# pcm5100_breakout_v10.net
KiCad netlist of a schematic drawn in EAGLE
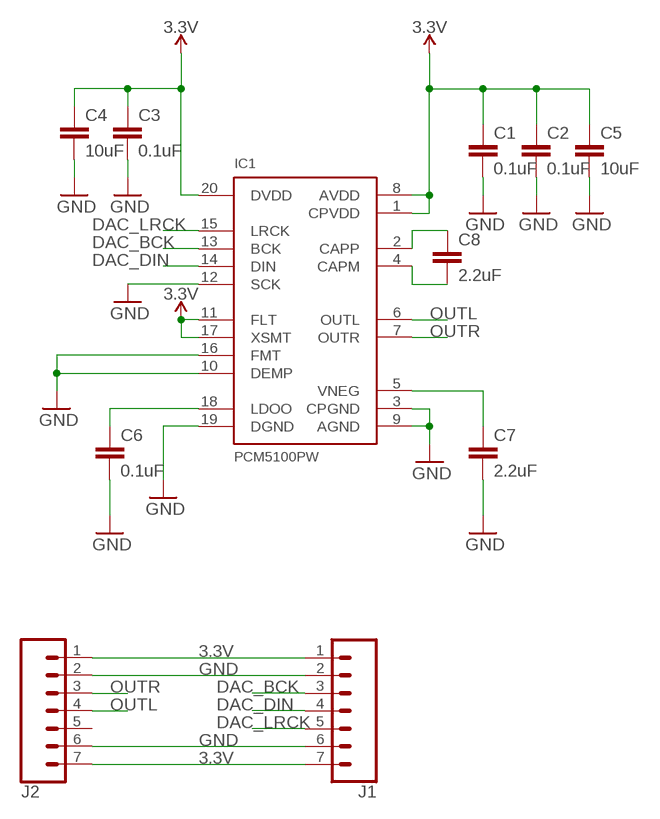
[diagram p0: schematic, sheet 1]

(export (version "E")
  (design (tool "Eeschema 10.0.6"))
  (components
    (comp (ref "C1")
      (value "0.1uF")
      (footprint "eagle-import:0603")
      (libsource (lib "eagle-import") (part "0.1UF-0603-25V-(+80/-20%)"))
    )
    (comp (ref "C2")
      (value "0.1uF")
      (footprint "eagle-import:0603")
      (libsource (lib "eagle-import") (part "0.1UF-0603-25V-(+80/-20%)"))
    )
    (comp (ref "C3")
      (value "0.1uF")
      (footprint "eagle-import:0603")
      (libsource (lib "eagle-import") (part "0.1UF-0603-25V-(+80/-20%)"))
    )
    (comp (ref "C4")
      (value "10uF")
      (footprint "eagle-import:0603")
      (libsource (lib "eagle-import") (part "10UF-0603-6.3V-20%"))
    )
    (comp (ref "C5")
      (value "10uF")
      (footprint "eagle-import:0603")
      (libsource (lib "eagle-import") (part "10UF-0603-6.3V-20%"))
    )
    (comp (ref "C6")
      (value "0.1uF")
      (footprint "eagle-import:0603")
      (libsource (lib "eagle-import") (part "0.1UF-0603-25V-(+80/-20%)"))
    )
    (comp (ref "C7")
      (value "2.2uF")
      (footprint "eagle-import:0603")
      (libsource (lib "eagle-import") (part "2.2UF-0603-10V-20%"))
    )
    (comp (ref "C8")
      (value "2.2uF")
      (footprint "eagle-import:0603")
      (libsource (lib "eagle-import") (part "2.2UF-0603-10V-20%"))
    )
    (comp (ref "IC1")
      (value "PCM5100PW")
      (footprint "eagle-import:SSOP20")
      (libsource (lib "eagle-import") (part "PCM5100PW"))
    )
    (comp (ref "J1")
      (value "CONN_07")
      (footprint "eagle-import:1X07")
      (libsource (lib "eagle-import") (part "CONN_07"))
    )
    (comp (ref "J2")
      (value "CONN_07")
      (footprint "eagle-import:1X07")
      (libsource (lib "eagle-import") (part "CONN_07"))
    )
  )
  (nets
    (net (code "1") (name "/DAC_BCK") (class "Default")
      (node (ref "IC1") (pin "13") (pinfunction "BCK_13") (pintype "input"))
      (node (ref "J1") (pin "3") (pinfunction "3_3") (pintype "passive"))
    )
    (net (code "2") (name "/DAC_DIN") (class "Default")
      (node (ref "IC1") (pin "14") (pinfunction "DIN_14") (pintype "input"))
      (node (ref "J1") (pin "4") (pinfunction "4_4") (pintype "passive"))
    )
    (net (code "3") (name "/DAC_LRCK") (class "Default")
      (node (ref "IC1") (pin "15") (pinfunction "LRCK_15") (pintype "input"))
      (node (ref "J1") (pin "5") (pinfunction "5_5") (pintype "passive"))
    )
    (net (code "4") (name "/OUTL") (class "Default")
      (node (ref "IC1") (pin "6") (pinfunction "OUTL_6") (pintype "output"))
      (node (ref "J2") (pin "4") (pinfunction "4_4") (pintype "passive"))
    )
    (net (code "5") (name "/OUTR") (class "Default")
      (node (ref "IC1") (pin "7") (pinfunction "OUTR_7") (pintype "output"))
      (node (ref "J2") (pin "3") (pinfunction "3_3") (pintype "passive"))
    )
    (net (code "6") (name "3.3V") (class "Default")
      (node (ref "C1") (pin "1") (pinfunction "1_1") (pintype "passive"))
      (node (ref "C2") (pin "1") (pinfunction "1_1") (pintype "passive"))
      (node (ref "C3") (pin "1") (pinfunction "1_1") (pintype "passive"))
      (node (ref "C4") (pin "1") (pinfunction "1_1") (pintype "passive"))
      (node (ref "C5") (pin "1") (pinfunction "1_1") (pintype "passive"))
      (node (ref "IC1") (pin "1") (pinfunction "CPVDD_1") (pintype "bidirectional"))
      (node (ref "IC1") (pin "11") (pinfunction "FLT_11") (pintype "input"))
      (node (ref "IC1") (pin "17") (pinfunction "XSMT_17") (pintype "input"))
      (node (ref "IC1") (pin "20") (pinfunction "DVDD_20") (pintype "power_in"))
      (node (ref "IC1") (pin "8") (pinfunction "AVDD_8") (pintype "power_in"))
      (node (ref "J1") (pin "1") (pinfunction "1_1") (pintype "passive"))
      (node (ref "J1") (pin "7") (pinfunction "7_7") (pintype "passive"))
      (node (ref "J2") (pin "1") (pinfunction "1_1") (pintype "passive"))
      (node (ref "J2") (pin "7") (pinfunction "7_7") (pintype "passive"))
    )
    (net (code "7") (name "GND") (class "Default")
      (node (ref "C1") (pin "2") (pinfunction "2_2") (pintype "passive"))
      (node (ref "C2") (pin "2") (pinfunction "2_2") (pintype "passive"))
      (node (ref "C3") (pin "2") (pinfunction "2_2") (pintype "passive"))
      (node (ref "C4") (pin "2") (pinfunction "2_2") (pintype "passive"))
      (node (ref "C5") (pin "2") (pinfunction "2_2") (pintype "passive"))
      (node (ref "C6") (pin "2") (pinfunction "2_2") (pintype "passive"))
      (node (ref "C7") (pin "2") (pinfunction "2_2") (pintype "passive"))
      (node (ref "IC1") (pin "10") (pinfunction "DEMP_10") (pintype "input"))
      (node (ref "IC1") (pin "12") (pinfunction "SCK_12") (pintype "input"))
      (node (ref "IC1") (pin "16") (pinfunction "FMT_16") (pintype "input"))
      (node (ref "IC1") (pin "19") (pinfunction "DGND_19") (pintype "power_in"))
      (node (ref "IC1") (pin "3") (pinfunction "CPGND_3") (pintype "bidirectional"))
      (node (ref "IC1") (pin "9") (pinfunction "AGND_9") (pintype "power_in"))
      (node (ref "J1") (pin "2") (pinfunction "2_2") (pintype "passive"))
      (node (ref "J1") (pin "6") (pinfunction "6_6") (pintype "passive"))
      (node (ref "J2") (pin "2") (pinfunction "2_2") (pintype "passive"))
      (node (ref "J2") (pin "6") (pinfunction "6_6") (pintype "passive"))
    )
    (net (code "8") (name "Net-(IC1-CAPM)") (class "Default")
      (node (ref "C8") (pin "2") (pinfunction "2_2") (pintype "passive"))
      (node (ref "IC1") (pin "4") (pinfunction "CAPM_4") (pintype "bidirectional"))
    )
    (net (code "9") (name "Net-(IC1-CAPP)") (class "Default")
      (node (ref "C8") (pin "1") (pinfunction "1_1") (pintype "passive"))
      (node (ref "IC1") (pin "2") (pinfunction "CAPP_2") (pintype "bidirectional"))
    )
    (net (code "10") (name "Net-(IC1-LDOO)") (class "Default")
      (node (ref "C6") (pin "1") (pinfunction "1_1") (pintype "passive"))
      (node (ref "IC1") (pin "18") (pinfunction "LDOO_18") (pintype "bidirectional"))
    )
    (net (code "11") (name "Net-(IC1-VNEG)") (class "Default")
      (node (ref "C7") (pin "1") (pinfunction "1_1") (pintype "passive"))
      (node (ref "IC1") (pin "5") (pinfunction "VNEG_5") (pintype "input"))
    )
    (net (code "12") (name "unconnected-(J2-Pad5)") (class "Default")
      (node (ref "J2") (pin "5") (pinfunction "5_5") (pintype "passive"))
    )
  )
)
